# ESP32_with_USBC.net
KiCad netlist of a schematic drawn in Altium Designer
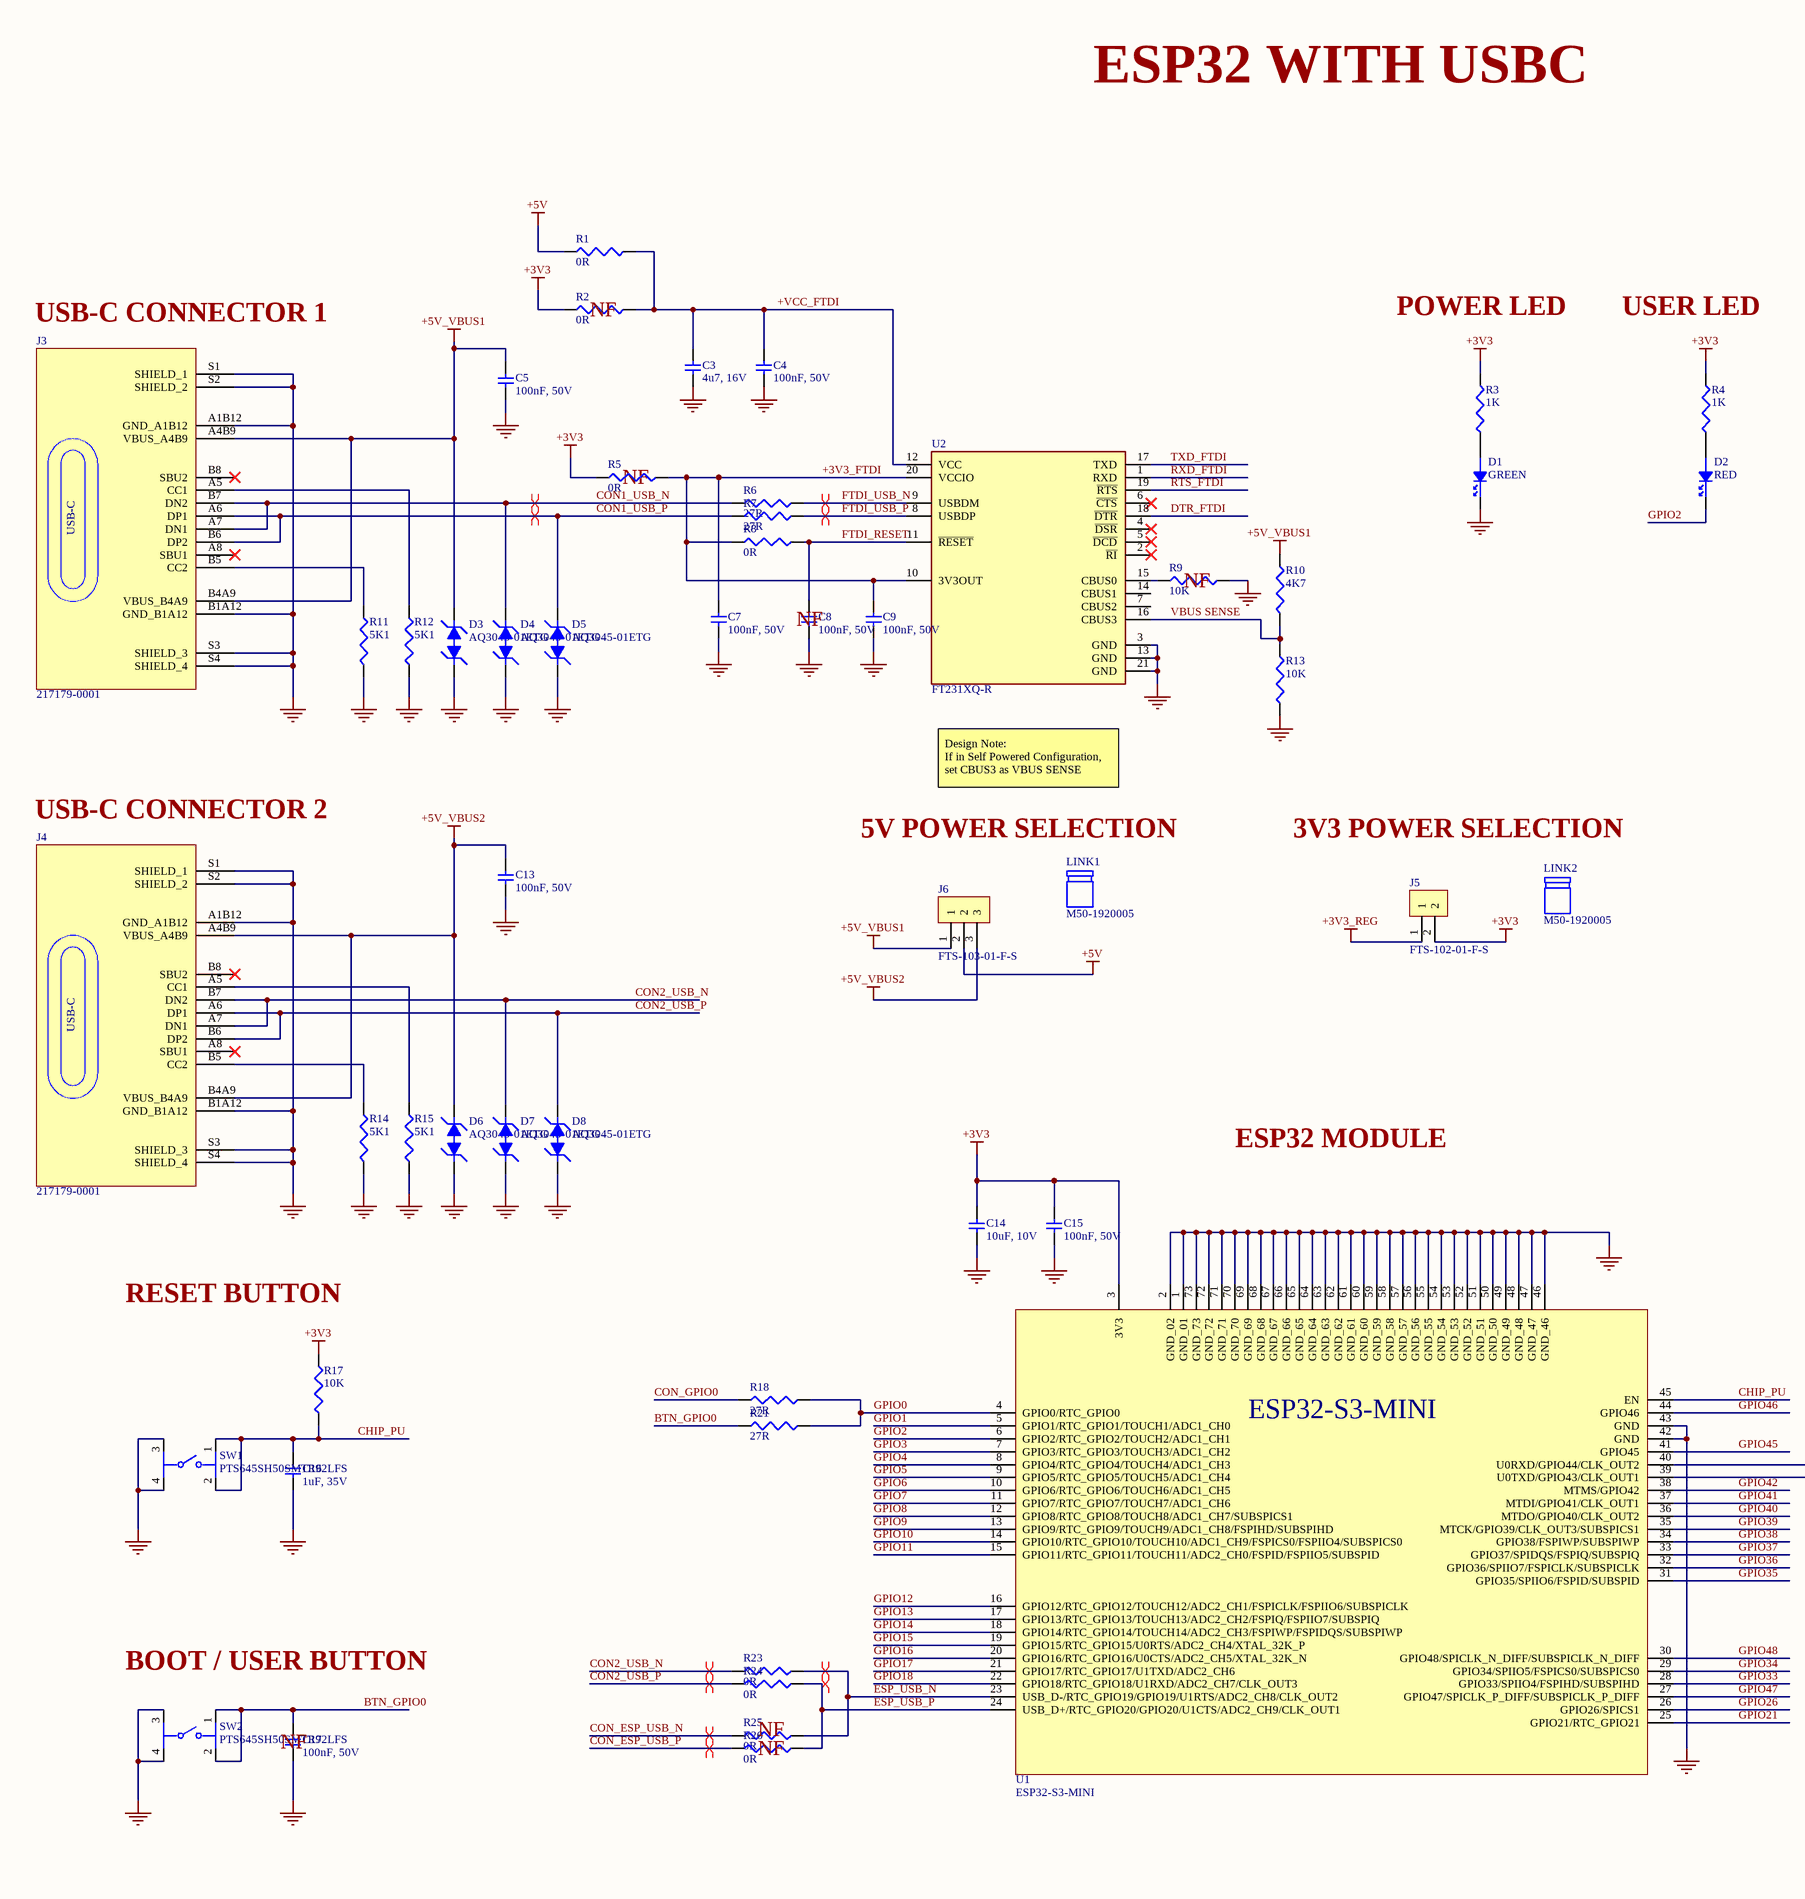
[diagram p0: ESP32 with USBC.SchDoc, left]
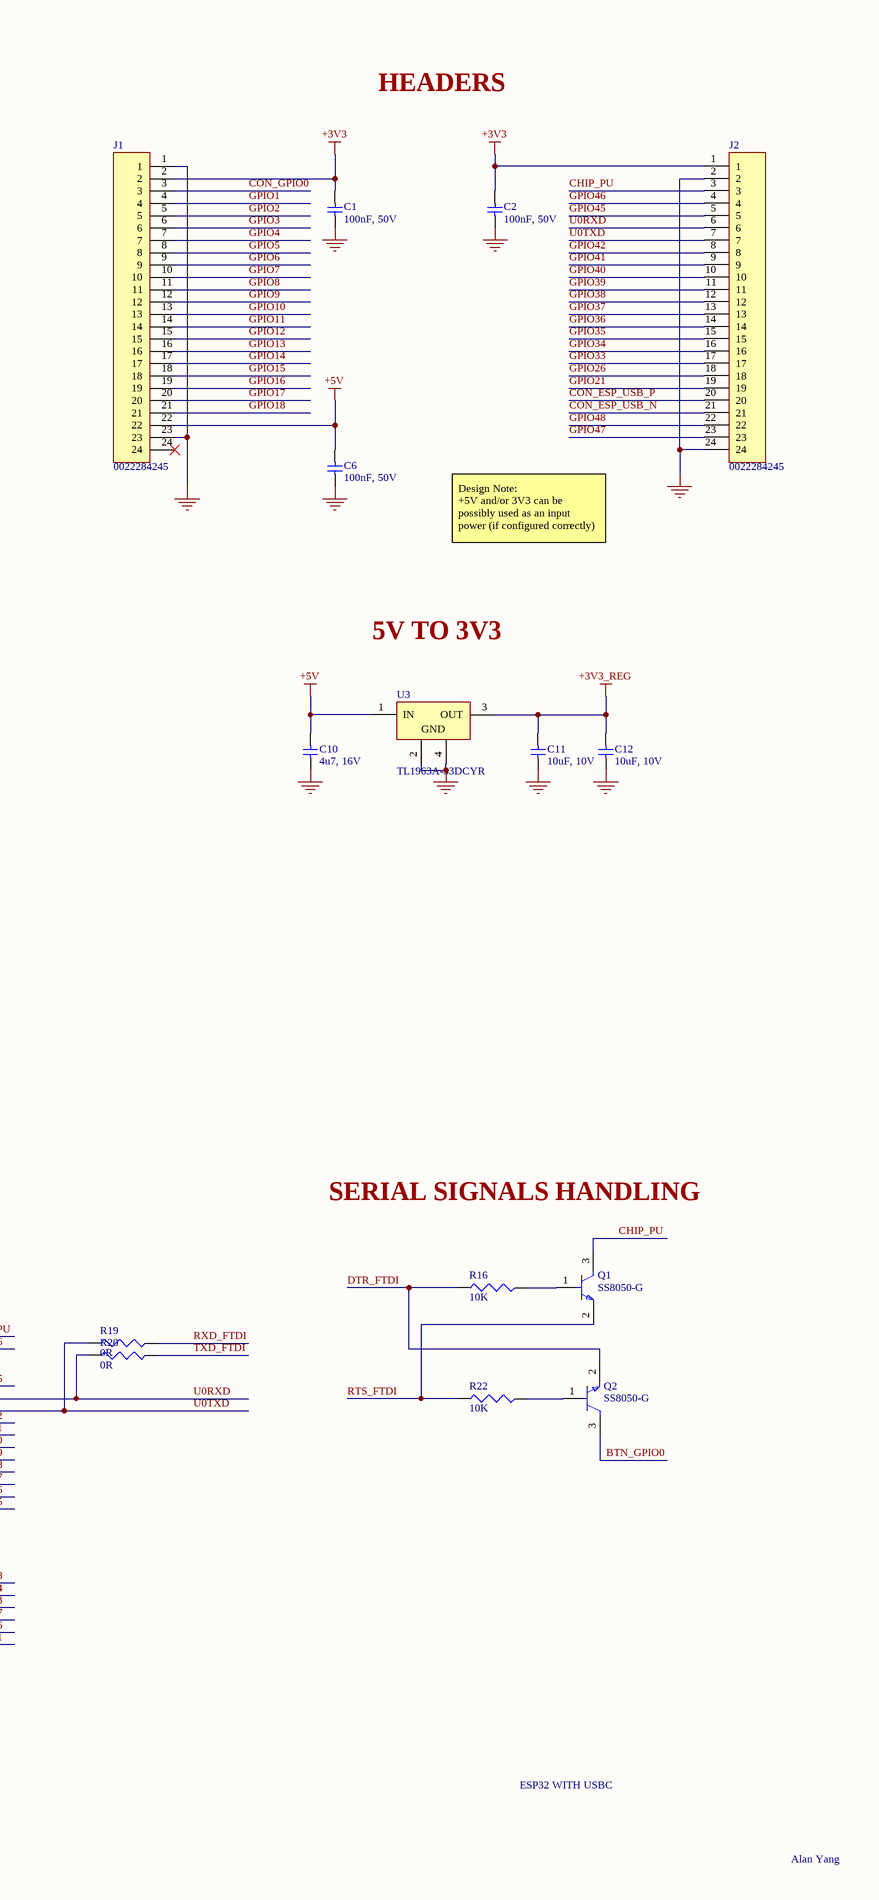
[diagram p1: ESP32 with USBC.SchDoc, right]

(export (version "E")
  (design (tool "Eeschema 10.0.6"))
  (components
    (comp (ref "C1")
      (value "100nF, 50V")
      (footprint "CAPC1005X55N")
      (description "CAP CER 0.1UF 50V X7R 0402")
      (fields
        (field (name "MANUFACTURER") "Samsung")
        (field (name "MANUFACTURER PART NUMBER") "CL05B104KB54PNC")
      )
      (libsource (lib "Schlib") (part "CL05B104KB54PNC"))
    )
    (comp (ref "C2")
      (value "100nF, 50V")
      (footprint "CAPC1005X55N")
      (description "CAP CER 0.1UF 50V X7R 0402")
      (fields
        (field (name "MANUFACTURER") "Samsung")
        (field (name "MANUFACTURER PART NUMBER") "CL05B104KB54PNC")
      )
      (libsource (lib "Schlib") (part "CL05B104KB54PNC"))
    )
    (comp (ref "C3")
      (value "4u7, 16V")
      (footprint "CAPC1005X55N")
      (description "CAP CER 4.7UF 16V X5R 0402")
      (fields
        (field (name "MANUFACTURER") "Samsung")
        (field (name "MANUFACTURER PART NUMBER") "CL05A475MO5NUNC")
      )
      (libsource (lib "Schlib") (part "CL05A475MO5NUNC"))
    )
    (comp (ref "C4")
      (value "100nF, 50V")
      (footprint "CAPC1005X55N")
      (description "CAP CER 0.1UF 50V X7R 0402")
      (fields
        (field (name "MANUFACTURER") "Samsung")
        (field (name "MANUFACTURER PART NUMBER") "CL05B104KB54PNC")
      )
      (libsource (lib "Schlib") (part "CL05B104KB54PNC"))
    )
    (comp (ref "C5")
      (value "100nF, 50V")
      (footprint "CAPC1005X55N")
      (description "CAP CER 0.1UF 50V X7R 0402")
      (fields
        (field (name "MANUFACTURER") "Samsung")
        (field (name "MANUFACTURER PART NUMBER") "CL05B104KB54PNC")
      )
      (libsource (lib "Schlib") (part "CL05B104KB54PNC"))
    )
    (comp (ref "C6")
      (value "100nF, 50V")
      (footprint "CAPC1005X55N")
      (description "CAP CER 0.1UF 50V X7R 0402")
      (fields
        (field (name "MANUFACTURER") "Samsung")
        (field (name "MANUFACTURER PART NUMBER") "CL05B104KB54PNC")
      )
      (libsource (lib "Schlib") (part "CL05B104KB54PNC"))
    )
    (comp (ref "C7")
      (value "100nF, 50V")
      (footprint "CAPC1005X55N")
      (description "CAP CER 0.1UF 50V X7R 0402")
      (fields
        (field (name "MANUFACTURER") "Samsung")
        (field (name "MANUFACTURER PART NUMBER") "CL05B104KB54PNC")
      )
      (libsource (lib "Schlib") (part "CL05B104KB54PNC"))
    )
    (comp (ref "C8")
      (value "100nF, 50V")
      (footprint "CAPC1005X55N")
      (description "CAP CER 0.1UF 50V X7R 0402")
      (fields
        (field (name "MANUFACTURER") "Samsung")
        (field (name "MANUFACTURER PART NUMBER") "CL05B104KB54PNC")
      )
      (libsource (lib "Schlib") (part "CL05B104KB54PNC"))
    )
    (comp (ref "C9")
      (value "100nF, 50V")
      (footprint "CAPC1005X55N")
      (description "CAP CER 0.1UF 50V X7R 0402")
      (fields
        (field (name "MANUFACTURER") "Samsung")
        (field (name "MANUFACTURER PART NUMBER") "CL05B104KB54PNC")
      )
      (libsource (lib "Schlib") (part "CL05B104KB54PNC"))
    )
    (comp (ref "C10")
      (value "4u7, 16V")
      (footprint "CAPC1005X55N")
      (description "CAP CER 4.7UF 16V X5R 0402")
      (fields
        (field (name "MANUFACTURER") "Samsung")
        (field (name "MANUFACTURER PART NUMBER") "CL05A475MO5NUNC")
      )
      (libsource (lib "Schlib") (part "CL05A475MO5NUNC"))
    )
    (comp (ref "C11")
      (value "10uF, 10V")
      (footprint "CAPC1005X55N")
      (description "CAP CER 10UF 10V X5R 0402")
      (fields
        (field (name "MANUFACTURER") "Samsung")
        (field (name "MANUFACTURER PART NUMBER") "CL05A106MP8NUB8")
      )
      (libsource (lib "Schlib") (part "CL05A106MP8NUB8"))
    )
    (comp (ref "C12")
      (value "10uF, 10V")
      (footprint "CAPC1005X55N")
      (description "CAP CER 10UF 10V X5R 0402")
      (fields
        (field (name "MANUFACTURER") "Samsung")
        (field (name "MANUFACTURER PART NUMBER") "CL05A106MP8NUB8")
      )
      (libsource (lib "Schlib") (part "CL05A106MP8NUB8"))
    )
    (comp (ref "C13")
      (value "100nF, 50V")
      (footprint "CAPC1005X55N")
      (description "CAP CER 0.1UF 50V X7R 0402")
      (fields
        (field (name "MANUFACTURER") "Samsung")
        (field (name "MANUFACTURER PART NUMBER") "CL05B104KB54PNC")
      )
      (libsource (lib "Schlib") (part "CL05B104KB54PNC"))
    )
    (comp (ref "C14")
      (value "10uF, 10V")
      (footprint "CAPC1005X55N")
      (description "CAP CER 10UF 10V X5R 0402")
      (fields
        (field (name "MANUFACTURER") "Samsung")
        (field (name "MANUFACTURER PART NUMBER") "CL05A106MP8NUB8")
      )
      (libsource (lib "Schlib") (part "CL05A106MP8NUB8"))
    )
    (comp (ref "C15")
      (value "100nF, 50V")
      (footprint "CAPC1005X55N")
      (description "CAP CER 0.1UF 50V X7R 0402")
      (fields
        (field (name "MANUFACTURER") "Samsung")
        (field (name "MANUFACTURER PART NUMBER") "CL05B104KB54PNC")
      )
      (libsource (lib "Schlib") (part "CL05B104KB54PNC"))
    )
    (comp (ref "C16")
      (value "1uF, 35V")
      (footprint "CAPC1005X55N")
      (description "CAP CER 1UF 35V X5R 0402")
      (fields
        (field (name "MANUFACTURER") "Samsung")
        (field (name "MANUFACTURER PART NUMBER") "CL05A105KL5NRNC")
      )
      (libsource (lib "Schlib") (part "CL05A105KL5NRNC"))
    )
    (comp (ref "C17")
      (value "100nF, 50V")
      (footprint "CAPC1005X55N")
      (description "CAP CER 0.1UF 50V X7R 0402")
      (fields
        (field (name "MANUFACTURER") "Samsung")
        (field (name "MANUFACTURER PART NUMBER") "CL05B104KB54PNC")
      )
      (libsource (lib "Schlib") (part "CL05B104KB54PNC"))
    )
    (comp (ref "D1")
      (value "GREEN")
      (footprint "LED0402G")
      (description "LED YLW-GRN 0402 SMD")
      (fields
        (field (name "MANUFACTURER") "Vishay")
        (field (name "MANUFACTURER PART NUMBER") "VLMG1500-GS08")
      )
      (libsource (lib "Schlib") (part "VLMG1500-GS08"))
    )
    (comp (ref "D2")
      (value "RED")
      (footprint "LED0402R")
      (description "LED RED 0402 SMD")
      (fields
        (field (name "MANUFACTURER") "Vishay")
        (field (name "MANUFACTURER PART NUMBER") "VLMS1500-GS08")
      )
      (libsource (lib "Schlib") (part "VLMS1500-GS08"))
    )
    (comp (ref "D3")
      (value "AQ3045-01ETG")
      (footprint "SOD882")
      (description "TVS DIODE 5.3VWM 12VC SOD882")
      (fields (field (name "MANUFACTURER") "Littelfuse") (field (name "LCSC PART NUMBER") "C3710326"))
      (libsource (lib "Schlib") (part "AQ3045-01ETG"))
    )
    (comp (ref "D4")
      (value "AQ3045-01ETG")
      (footprint "SOD882")
      (description "TVS DIODE 5.3VWM 12VC SOD882")
      (fields (field (name "MANUFACTURER") "Littelfuse") (field (name "LCSC PART NUMBER") "C3710326"))
      (libsource (lib "Schlib") (part "AQ3045-01ETG"))
    )
    (comp (ref "D5")
      (value "AQ3045-01ETG")
      (footprint "SOD882")
      (description "TVS DIODE 5.3VWM 12VC SOD882")
      (fields (field (name "MANUFACTURER") "Littelfuse") (field (name "LCSC PART NUMBER") "C3710326"))
      (libsource (lib "Schlib") (part "AQ3045-01ETG"))
    )
    (comp (ref "D6")
      (value "AQ3045-01ETG")
      (footprint "SOD882")
      (description "TVS DIODE 5.3VWM 12VC SOD882")
      (fields (field (name "MANUFACTURER") "Littelfuse") (field (name "LCSC PART NUMBER") "C3710326"))
      (libsource (lib "Schlib") (part "AQ3045-01ETG"))
    )
    (comp (ref "D7")
      (value "AQ3045-01ETG")
      (footprint "SOD882")
      (description "TVS DIODE 5.3VWM 12VC SOD882")
      (fields (field (name "MANUFACTURER") "Littelfuse") (field (name "LCSC PART NUMBER") "C3710326"))
      (libsource (lib "Schlib") (part "AQ3045-01ETG"))
    )
    (comp (ref "D8")
      (value "AQ3045-01ETG")
      (footprint "SOD882")
      (description "TVS DIODE 5.3VWM 12VC SOD882")
      (fields (field (name "MANUFACTURER") "Littelfuse") (field (name "LCSC PART NUMBER") "C3710326"))
      (libsource (lib "Schlib") (part "AQ3045-01ETG"))
    )
    (comp (ref "J1")
      (value "0022284245")
      (footprint "HDR_1X24_2.54MM")
      (description "CONN HEADER VERT 24POS 2.54MM")
      (fields (field (name "MANUFACTURER") "Molex") (field (name "MANUFACTURER PART NUMBER") "22-28-4245"))
      (libsource (lib "Schlib") (part "0022284245"))
    )
    (comp (ref "J2")
      (value "0022284245")
      (footprint "HDR_1X24_2.54MM")
      (description "CONN HEADER VERT 24POS 2.54MM")
      (fields (field (name "MANUFACTURER") "Molex") (field (name "MANUFACTURER PART NUMBER") "22-28-4245"))
      (libsource (lib "") (part "0022284245_1"))
    )
    (comp (ref "J3")
      (value "217179-0001")
      (footprint "FP-2171790001-MFG")
      (description "CONN RCP USB2.0 TYP C 24P SMD RA")
      (fields (field (name "MANUFACTURER") "Molex") (field (name "LCSC PART NUMBER") "C3197684"))
      (libsource (lib "Schlib") (part "217179-0001"))
    )
    (comp (ref "J4")
      (value "217179-0001")
      (footprint "FP-2171790001-MFG")
      (description "CONN RCP USB2.0 TYP C 24P SMD RA")
      (fields (field (name "MANUFACTURER") "Molex") (field (name "LCSC PART NUMBER") "C3197684"))
      (libsource (lib "Schlib") (part "217179-0001"))
    )
    (comp (ref "J5")
      (value "FTS-102-01-F-S")
      (footprint "HDR_1X2_1.27MM")
      (description "CONN HEADER VERT 2POS 1.27MM")
      (fields (field (name "MANUFACTURER") "Samtec") (field (name "LCSC PART NUMBER") "C6045317"))
      (libsource (lib "Schlib") (part "FTS-102-01-F-S"))
    )
    (comp (ref "J6")
      (value "FTS-103-01-F-S")
      (footprint "HDR_1X3_1.27MM")
      (description "CONN HEADER VERT 3POS 1.27MM")
      (fields (field (name "MANUFACTURER") "Samtec") (field (name "LCSC PART NUMBER") "C3333578"))
      (libsource (lib "Schlib") (part "FTS-103-01-F-S"))
    )
    (comp (ref "LINK1")
      (value "M50-1920005")
      (description "CONN SHUNT 1.27MM RED")
      (fields (field (name "MANUFACTURER") "Harwin") (field (name "LCSC PART NUMBER") "C6985646"))
      (libsource (lib "Schlib") (part "M50-1920005"))
    )
    (comp (ref "LINK2")
      (value "M50-1920005")
      (description "CONN SHUNT 1.27MM RED")
      (fields (field (name "MANUFACTURER") "Harwin") (field (name "LCSC PART NUMBER") "C6985646"))
      (libsource (lib "Schlib") (part "M50-1920005"))
    )
    (comp (ref "Q1")
      (value "SS8050-G")
      (footprint "FP-SS8050-G-IPC_B")
      (description "TRANS NPN 25V 1.5A SOT-23-3")
      (fields (field (name "MANUFACTURER") "Comchip") (field (name "LCSC PART NUMBER") "C164886"))
      (libsource (lib "Schlib") (part "SS8050-G"))
    )
    (comp (ref "Q2")
      (value "SS8050-G")
      (footprint "FP-SS8050-G-IPC_B")
      (description "TRANS NPN 25V 1.5A SOT-23-3")
      (fields (field (name "MANUFACTURER") "Comchip") (field (name "LCSC PART NUMBER") "C164886"))
      (libsource (lib "Schlib") (part "SS8050-G"))
    )
    (comp (ref "R1")
      (value "0R")
      (footprint "RESC1005X37N")
      (description "RES 0 OHM JUMPER 1/16W 0402")
      (fields
        (field (name "MANUFACTURER") "Yageo")
        (field (name "MANUFACTURER PART NUMBER") "RC0402JR-070RL")
      )
      (libsource (lib "Schlib") (part "RC0402JR-070RL"))
    )
    (comp (ref "R2")
      (value "0R")
      (footprint "RESC1005X37N")
      (description "RES 0 OHM JUMPER 1/16W 0402")
      (fields
        (field (name "MANUFACTURER") "Yageo")
        (field (name "MANUFACTURER PART NUMBER") "RC0402JR-070RL")
      )
      (libsource (lib "Schlib") (part "RC0402JR-070RL"))
    )
    (comp (ref "R3")
      (value "1K")
      (footprint "RESC1005X37N")
      (description "RES 1K OHM 1% 1/16W 0402")
      (fields
        (field (name "MANUFACTURER") "Yageo")
        (field (name "MANUFACTURER PART NUMBER") "RC0402FR-071KL")
      )
      (libsource (lib "Schlib") (part "RC0402FR-071KL"))
    )
    (comp (ref "R4")
      (value "1K")
      (footprint "RESC1005X37N")
      (description "RES 1K OHM 1% 1/16W 0402")
      (fields
        (field (name "MANUFACTURER") "Yageo")
        (field (name "MANUFACTURER PART NUMBER") "RC0402FR-071KL")
      )
      (libsource (lib "Schlib") (part "RC0402FR-071KL"))
    )
    (comp (ref "R5")
      (value "0R")
      (footprint "RESC1005X37N")
      (description "RES 0 OHM JUMPER 1/16W 0402")
      (fields
        (field (name "MANUFACTURER") "Yageo")
        (field (name "MANUFACTURER PART NUMBER") "RC0402JR-070RL")
      )
      (libsource (lib "Schlib") (part "RC0402JR-070RL"))
    )
    (comp (ref "R6")
      (value "27R")
      (footprint "RESC1005X37N")
      (description "RES 27.4 OHM 1% 1/16W 0402")
      (fields
        (field (name "MANUFACTURER") "Yageo")
        (field (name "MANUFACTURER PART NUMBER") "RC0402FR-0727R4L")
      )
      (libsource (lib "Schlib") (part "RC0402FR-0727R4L"))
    )
    (comp (ref "R7")
      (value "27R")
      (footprint "RESC1005X37N")
      (description "RES 27.4 OHM 1% 1/16W 0402")
      (fields
        (field (name "MANUFACTURER") "Yageo")
        (field (name "MANUFACTURER PART NUMBER") "RC0402FR-0727R4L")
      )
      (libsource (lib "Schlib") (part "RC0402FR-0727R4L"))
    )
    (comp (ref "R8")
      (value "0R")
      (footprint "RESC1005X37N")
      (description "RES 0 OHM JUMPER 1/16W 0402")
      (fields
        (field (name "MANUFACTURER") "Yageo")
        (field (name "MANUFACTURER PART NUMBER") "RC0402JR-070RL")
      )
      (libsource (lib "Schlib") (part "RC0402JR-070RL"))
    )
    (comp (ref "R9")
      (value "10K")
      (footprint "RESC1005X37N")
      (description "RES SMD 10K OHM 1% 1/16W 0402")
      (fields
        (field (name "MANUFACTURER") "Yageo")
        (field (name "MANUFACTURER PART NUMBER") "AC0402FR-0710KL")
      )
      (libsource (lib "Schlib") (part "AC0402FR-0710KL"))
    )
    (comp (ref "R10")
      (value "4K7")
      (footprint "RESC1005X37N")
      (description "RES 4.7K OHM 1% 1/16W 0402")
      (fields
        (field (name "MANUFACTURER") "Yageo")
        (field (name "MANUFACTURER PART NUMBER") "RC0402FR-074K7L")
      )
      (libsource (lib "Schlib") (part "RC0402FR-074K7L"))
    )
    (comp (ref "R11")
      (value "5K1")
      (footprint "RESC1005X37N")
      (description "RES SMD 5.1K OHM 1% 1/16W 0402")
      (fields
        (field (name "MANUFACTURER") "Yageo")
        (field (name "MANUFACTURER PART NUMBER") "AC0402FR-075K1L")
      )
      (libsource (lib "Schlib") (part "AC0402FR-075K1L"))
    )
    (comp (ref "R12")
      (value "5K1")
      (footprint "RESC1005X37N")
      (description "RES SMD 5.1K OHM 1% 1/16W 0402")
      (fields
        (field (name "MANUFACTURER") "Yageo")
        (field (name "MANUFACTURER PART NUMBER") "AC0402FR-075K1L")
      )
      (libsource (lib "Schlib") (part "AC0402FR-075K1L"))
    )
    (comp (ref "R13")
      (value "10K")
      (footprint "RESC1005X37N")
      (description "RES SMD 10K OHM 1% 1/16W 0402")
      (fields
        (field (name "MANUFACTURER") "Yageo")
        (field (name "MANUFACTURER PART NUMBER") "AC0402FR-0710KL")
      )
      (libsource (lib "Schlib") (part "AC0402FR-0710KL"))
    )
    (comp (ref "R14")
      (value "5K1")
      (footprint "RESC1005X37N")
      (description "RES SMD 5.1K OHM 1% 1/16W 0402")
      (fields
        (field (name "MANUFACTURER") "Yageo")
        (field (name "MANUFACTURER PART NUMBER") "AC0402FR-075K1L")
      )
      (libsource (lib "Schlib") (part "AC0402FR-075K1L"))
    )
    (comp (ref "R15")
      (value "5K1")
      (footprint "RESC1005X37N")
      (description "RES SMD 5.1K OHM 1% 1/16W 0402")
      (fields
        (field (name "MANUFACTURER") "Yageo")
        (field (name "MANUFACTURER PART NUMBER") "AC0402FR-075K1L")
      )
      (libsource (lib "Schlib") (part "AC0402FR-075K1L"))
    )
    (comp (ref "R16")
      (value "10K")
      (footprint "RESC1005X37N")
      (description "RES SMD 10K OHM 1% 1/16W 0402")
      (fields
        (field (name "MANUFACTURER") "Yageo")
        (field (name "MANUFACTURER PART NUMBER") "AC0402FR-0710KL")
      )
      (libsource (lib "Schlib") (part "AC0402FR-0710KL"))
    )
    (comp (ref "R17")
      (value "10K")
      (footprint "RESC1005X37N")
      (description "RES SMD 10K OHM 1% 1/16W 0402")
      (fields
        (field (name "MANUFACTURER") "Yageo")
        (field (name "MANUFACTURER PART NUMBER") "AC0402FR-0710KL")
      )
      (libsource (lib "Schlib") (part "AC0402FR-0710KL"))
    )
    (comp (ref "R18")
      (value "27R")
      (footprint "RESC1005X37N")
      (description "RES 27.4 OHM 1% 1/16W 0402")
      (fields
        (field (name "MANUFACTURER") "Yageo")
        (field (name "MANUFACTURER PART NUMBER") "RC0402FR-0727R4L")
      )
      (libsource (lib "Schlib") (part "RC0402FR-0727R4L"))
    )
    (comp (ref "R19")
      (value "0R")
      (footprint "RESC1005X37N")
      (description "RES 0 OHM JUMPER 1/16W 0402")
      (fields
        (field (name "MANUFACTURER") "Yageo")
        (field (name "MANUFACTURER PART NUMBER") "RC0402JR-070RL")
      )
      (libsource (lib "Schlib") (part "RC0402JR-070RL"))
    )
    (comp (ref "R20")
      (value "0R")
      (footprint "RESC1005X37N")
      (description "RES 0 OHM JUMPER 1/16W 0402")
      (fields
        (field (name "MANUFACTURER") "Yageo")
        (field (name "MANUFACTURER PART NUMBER") "RC0402JR-070RL")
      )
      (libsource (lib "Schlib") (part "RC0402JR-070RL"))
    )
    (comp (ref "R21")
      (value "27R")
      (footprint "RESC1005X37N")
      (description "RES 27.4 OHM 1% 1/16W 0402")
      (fields
        (field (name "MANUFACTURER") "Yageo")
        (field (name "MANUFACTURER PART NUMBER") "RC0402FR-0727R4L")
      )
      (libsource (lib "Schlib") (part "RC0402FR-0727R4L"))
    )
    (comp (ref "R22")
      (value "10K")
      (footprint "RESC1005X37N")
      (description "RES SMD 10K OHM 1% 1/16W 0402")
      (fields
        (field (name "MANUFACTURER") "Yageo")
        (field (name "MANUFACTURER PART NUMBER") "AC0402FR-0710KL")
      )
      (libsource (lib "Schlib") (part "AC0402FR-0710KL"))
    )
    (comp (ref "R23")
      (value "0R")
      (footprint "RESC1005X37N")
      (description "RES 0 OHM JUMPER 1/16W 0402")
      (fields
        (field (name "MANUFACTURER") "Yageo")
        (field (name "MANUFACTURER PART NUMBER") "RC0402JR-070RL")
      )
      (libsource (lib "Schlib") (part "RC0402JR-070RL"))
    )
    (comp (ref "R24")
      (value "0R")
      (footprint "RESC1005X37N")
      (description "RES 0 OHM JUMPER 1/16W 0402")
      (fields
        (field (name "MANUFACTURER") "Yageo")
        (field (name "MANUFACTURER PART NUMBER") "RC0402JR-070RL")
      )
      (libsource (lib "Schlib") (part "RC0402JR-070RL"))
    )
    (comp (ref "R25")
      (value "0R")
      (footprint "RESC1005X37N")
      (description "RES 0 OHM JUMPER 1/16W 0402")
      (fields
        (field (name "MANUFACTURER") "Yageo")
        (field (name "MANUFACTURER PART NUMBER") "RC0402JR-070RL")
      )
      (libsource (lib "Schlib") (part "RC0402JR-070RL"))
    )
    (comp (ref "R26")
      (value "0R")
      (footprint "RESC1005X37N")
      (description "RES 0 OHM JUMPER 1/16W 0402")
      (fields
        (field (name "MANUFACTURER") "Yageo")
        (field (name "MANUFACTURER PART NUMBER") "RC0402JR-070RL")
      )
      (libsource (lib "Schlib") (part "RC0402JR-070RL"))
    )
    (comp (ref "SW1")
      (value "PTS645SH50SMTR92LFS")
      (footprint "FP-PTS645SH50SMTR92LFS-MFG")
      (description "SWITCH TACTILE SPST-NO 0.05A 12V")
      (fields (field (name "MANUFACTURER") "ITT C&K") (field (name "LCSC PART NUMBER") "C221869"))
      (libsource (lib "Schlib") (part "PTS645SH50SMTR92LFS"))
    )
    (comp (ref "SW2")
      (value "PTS645SH50SMTR92LFS")
      (footprint "FP-PTS645SH50SMTR92LFS-MFG")
      (description "SWITCH TACTILE SPST-NO 0.05A 12V")
      (fields (field (name "MANUFACTURER") "ITT C&K") (field (name "LCSC PART NUMBER") "C221869"))
      (libsource (lib "Schlib") (part "PTS645SH50SMTR92LFS"))
    )
    (comp (ref "U1")
      (value "ESP32-S3-MINI")
      (footprint "XCVR_ESP32-S3-MINI-1-N8")
      (description "SMD module, ESP32-S3FN8, 8 MB SPI flash, PCB antenna")
      (fields
        (field (name "MANUFACTURER") "Espressif Systems")
        (field (name "MANUFACTURER PART NUMBER") "ESP32-S3-MINI-1-N8")
      )
      (libsource (lib "Schlib") (part "ESP32-S3-MINI-1-N8"))
    )
    (comp (ref "U2")
      (value "FT231XQ-R")
      (footprint "FP-QFN-20-IPC_B")
      (description "IC USB SERIAL FULL UART 20QFN")
      (fields (field (name "MANUFACTURER") "FTDI") (field (name "LCSC PART NUMBER") "C132159"))
      (libsource (lib "Schlib") (part "FT231XQ-R"))
    )
    (comp (ref "U3")
      (value "TL1963A-33DCYR")
      (footprint "DCY0004A_N")
      (description "IC REG LIN 3.3V 1.5A SOT-223-4")
      (fields (field (name "MANUFACTURER") "Texas Instruments") (field (name "LCSC PART NUMBER") "C181262"))
      (libsource (lib "Schlib") (part "TL1963A-33DCYR"))
    )
  )
  (nets
    (net (code "1") (name "+3V3") (class "Default")
      (node (ref "C1") (pin "2") (pinfunction "2_2") (pintype "passive"))
      (node (ref "C14") (pin "2") (pinfunction "2_2") (pintype "passive"))
      (node (ref "C15") (pin "2") (pinfunction "2_2") (pintype "passive"))
      (node (ref "C2") (pin "2") (pinfunction "2_2") (pintype "passive"))
      (node (ref "J1") (pin "2") (pinfunction "2_2") (pintype "passive"))
      (node (ref "J2") (pin "1") (pinfunction "1_1") (pintype "passive"))
      (node (ref "J5") (pin "2") (pinfunction "2_2") (pintype "passive"))
      (node (ref "R17") (pin "2") (pinfunction "2_2") (pintype "passive"))
      (node (ref "R2") (pin "1") (pinfunction "1_1") (pintype "passive"))
      (node (ref "R3") (pin "2") (pinfunction "2_2") (pintype "passive"))
      (node (ref "R4") (pin "2") (pinfunction "2_2") (pintype "passive"))
      (node (ref "R5") (pin "1") (pinfunction "1_1") (pintype "passive"))
      (node (ref "U1") (pin "3") (pinfunction "3V3_3") (pintype "passive"))
    )
    (net (code "2") (name "+3V3_REG") (class "Default")
      (node (ref "C11") (pin "2") (pinfunction "2_2") (pintype "passive"))
      (node (ref "C12") (pin "2") (pinfunction "2_2") (pintype "passive"))
      (node (ref "J5") (pin "1") (pinfunction "1_1") (pintype "passive"))
      (node (ref "U3") (pin "3") (pinfunction "OUT_3") (pintype "power_in"))
    )
    (net (code "3") (name "+5V") (class "Default")
      (node (ref "C10") (pin "2") (pinfunction "2_2") (pintype "passive"))
      (node (ref "C6") (pin "2") (pinfunction "2_2") (pintype "passive"))
      (node (ref "J1") (pin "22") (pinfunction "22_22") (pintype "passive"))
      (node (ref "J6") (pin "2") (pinfunction "2_2") (pintype "passive"))
      (node (ref "R1") (pin "1") (pinfunction "1_1") (pintype "passive"))
      (node (ref "U3") (pin "1") (pinfunction "IN_1") (pintype "power_in"))
    )
    (net (code "4") (name "+5V_VBUS1") (class "Default")
      (node (ref "C5") (pin "2") (pinfunction "2_2") (pintype "passive"))
      (node (ref "D3") (pin "2") (pinfunction "2_2") (pintype "passive"))
      (node (ref "J3") (pin "A4B9") (pinfunction "VBUS_A4B9_A4B9") (pintype "passive"))
      (node (ref "J3") (pin "B4A9") (pinfunction "VBUS_B4A9_B4A9") (pintype "passive"))
      (node (ref "J6") (pin "1") (pinfunction "1_1") (pintype "passive"))
      (node (ref "R10") (pin "2") (pinfunction "2_2") (pintype "passive"))
    )
    (net (code "5") (name "+5V_VBUS2") (class "Default")
      (node (ref "C13") (pin "2") (pinfunction "2_2") (pintype "passive"))
      (node (ref "D6") (pin "2") (pinfunction "2_2") (pintype "passive"))
      (node (ref "J4") (pin "A4B9") (pinfunction "VBUS_A4B9_A4B9") (pintype "passive"))
      (node (ref "J4") (pin "B4A9") (pinfunction "VBUS_B4A9_B4A9") (pintype "passive"))
      (node (ref "J6") (pin "3") (pinfunction "3_3") (pintype "passive"))
    )
    (net (code "6") (name "/+3V3_FTDI") (class "Default")
      (node (ref "C7") (pin "2") (pinfunction "2_2") (pintype "passive"))
      (node (ref "C9") (pin "2") (pinfunction "2_2") (pintype "passive"))
      (node (ref "R5") (pin "2") (pinfunction "2_2") (pintype "passive"))
      (node (ref "R8") (pin "1") (pinfunction "1_1") (pintype "passive"))
      (node (ref "U2") (pin "10") (pinfunction "3V3OUT_10") (pintype "passive"))
      (node (ref "U2") (pin "20") (pinfunction "VCCIO_20") (pintype "passive"))
    )
    (net (code "7") (name "/+VCC_FTDI") (class "Default")
      (node (ref "C3") (pin "1") (pinfunction "1_1") (pintype "passive"))
      (node (ref "C4") (pin "2") (pinfunction "2_2") (pintype "passive"))
      (node (ref "R1") (pin "2") (pinfunction "2_2") (pintype "passive"))
      (node (ref "R2") (pin "2") (pinfunction "2_2") (pintype "passive"))
      (node (ref "U2") (pin "12") (pinfunction "VCC_12") (pintype "passive"))
    )
    (net (code "8") (name "/BTN_GPIO0") (class "Default")
      (node (ref "C17") (pin "2") (pinfunction "2_2") (pintype "passive"))
      (node (ref "Q2") (pin "3") (pinfunction "C_3") (pintype "passive"))
      (node (ref "R21") (pin "1") (pinfunction "1_1") (pintype "passive"))
      (node (ref "SW2") (pin "1") (pinfunction "1_1") (pintype "passive"))
      (node (ref "SW2") (pin "2") (pinfunction "2_2") (pintype "passive"))
    )
    (net (code "9") (name "/CHIP_PU") (class "Default")
      (node (ref "C16") (pin "2") (pinfunction "2_2") (pintype "passive"))
      (node (ref "J2") (pin "3") (pinfunction "3_3") (pintype "passive"))
      (node (ref "Q1") (pin "3") (pinfunction "C_3") (pintype "passive"))
      (node (ref "R17") (pin "1") (pinfunction "1_1") (pintype "passive"))
      (node (ref "SW1") (pin "1") (pinfunction "1_1") (pintype "passive"))
      (node (ref "SW1") (pin "2") (pinfunction "2_2") (pintype "passive"))
      (node (ref "U1") (pin "45") (pinfunction "EN_45") (pintype "passive"))
    )
    (net (code "10") (name "/CON1_USB_N") (class "Default")
      (node (ref "D4") (pin "2") (pinfunction "2_2") (pintype "passive"))
      (node (ref "J3") (pin "A7") (pinfunction "DN1_A7") (pintype "passive"))
      (node (ref "J3") (pin "B7") (pinfunction "DN2_B7") (pintype "passive"))
      (node (ref "R6") (pin "1") (pinfunction "1_1") (pintype "passive"))
    )
    (net (code "11") (name "/CON1_USB_P") (class "Default")
      (node (ref "D5") (pin "2") (pinfunction "2_2") (pintype "passive"))
      (node (ref "J3") (pin "A6") (pinfunction "DP1_A6") (pintype "passive"))
      (node (ref "J3") (pin "B6") (pinfunction "DP2_B6") (pintype "passive"))
      (node (ref "R7") (pin "1") (pinfunction "1_1") (pintype "passive"))
    )
    (net (code "12") (name "/CON2_USB_N") (class "Default")
      (node (ref "D7") (pin "2") (pinfunction "2_2") (pintype "passive"))
      (node (ref "J4") (pin "A7") (pinfunction "DN1_A7") (pintype "passive"))
      (node (ref "J4") (pin "B7") (pinfunction "DN2_B7") (pintype "passive"))
      (node (ref "R23") (pin "1") (pinfunction "1_1") (pintype "passive"))
    )
    (net (code "13") (name "/CON2_USB_P") (class "Default")
      (node (ref "D8") (pin "2") (pinfunction "2_2") (pintype "passive"))
      (node (ref "J4") (pin "A6") (pinfunction "DP1_A6") (pintype "passive"))
      (node (ref "J4") (pin "B6") (pinfunction "DP2_B6") (pintype "passive"))
      (node (ref "R24") (pin "1") (pinfunction "1_1") (pintype "passive"))
    )
    (net (code "14") (name "/CON_ESP_USB_N") (class "Default")
      (node (ref "J2") (pin "21") (pinfunction "21_21") (pintype "passive"))
      (node (ref "R25") (pin "1") (pinfunction "1_1") (pintype "passive"))
    )
    (net (code "15") (name "/CON_ESP_USB_P") (class "Default")
      (node (ref "J2") (pin "20") (pinfunction "20_20") (pintype "passive"))
      (node (ref "R26") (pin "1") (pinfunction "1_1") (pintype "passive"))
    )
    (net (code "16") (name "/CON_GPIO0") (class "Default")
      (node (ref "J1") (pin "3") (pinfunction "3_3") (pintype "passive"))
      (node (ref "R18") (pin "1") (pinfunction "1_1") (pintype "passive"))
    )
    (net (code "17") (name "/DTR_FTDI") (class "Default")
      (node (ref "Q2") (pin "2") (pinfunction "E_2") (pintype "passive"))
      (node (ref "R16") (pin "1") (pinfunction "1_1") (pintype "passive"))
      (node (ref "U2") (pin "18") (pinfunction "~{DTR}_18") (pintype "passive"))
    )
    (net (code "18") (name "/ESP_USB_N") (class "Default")
      (node (ref "R23") (pin "2") (pinfunction "2_2") (pintype "passive"))
      (node (ref "R25") (pin "2") (pinfunction "2_2") (pintype "passive"))
      (node (ref "U1") (pin "23") (pinfunction "USB_D-/RTC_GPIO19/GPIO19/U1RTS/ADC2_CH8/CLK_OUT2_23") (pintype "passive"))
    )
    (net (code "19") (name "/ESP_USB_P") (class "Default")
      (node (ref "R24") (pin "2") (pinfunction "2_2") (pintype "passive"))
      (node (ref "R26") (pin "2") (pinfunction "2_2") (pintype "passive"))
      (node (ref "U1") (pin "24") (pinfunction "USB_D+/RTC_GPIO20/GPIO20/U1CTS/ADC2_CH9/CLK_OUT1_24") (pintype "passive"))
    )
    (net (code "20") (name "/FTDI_RESET") (class "Default")
      (node (ref "C8") (pin "2") (pinfunction "2_2") (pintype "passive"))
      (node (ref "R8") (pin "2") (pinfunction "2_2") (pintype "passive"))
      (node (ref "U2") (pin "11") (pinfunction "~{RESET}_11") (pintype "passive"))
    )
    (net (code "21") (name "/FTDI_USB_N") (class "Default")
      (node (ref "R6") (pin "2") (pinfunction "2_2") (pintype "passive"))
      (node (ref "U2") (pin "9") (pinfunction "USBDM_9") (pintype "passive"))
    )
    (net (code "22") (name "/FTDI_USB_P") (class "Default")
      (node (ref "R7") (pin "2") (pinfunction "2_2") (pintype "passive"))
      (node (ref "U2") (pin "8") (pinfunction "USBDP_8") (pintype "passive"))
    )
    (net (code "23") (name "/GPIO0") (class "Default")
      (node (ref "R18") (pin "2") (pinfunction "2_2") (pintype "passive"))
      (node (ref "R21") (pin "2") (pinfunction "2_2") (pintype "passive"))
      (node (ref "U1") (pin "4") (pinfunction "GPIO0/RTC_GPIO0_4") (pintype "passive"))
    )
    (net (code "24") (name "/GPIO1") (class "Default")
      (node (ref "J1") (pin "4") (pinfunction "4_4") (pintype "passive"))
      (node (ref "U1") (pin "5") (pinfunction "GPIO1/RTC_GPIO1/TOUCH1/ADC1_CH0_5") (pintype "passive"))
    )
    (net (code "25") (name "/GPIO2") (class "Default")
      (node (ref "D2") (pin "1") (pinfunction "1_1") (pintype "passive"))
      (node (ref "J1") (pin "5") (pinfunction "5_5") (pintype "passive"))
      (node (ref "U1") (pin "6") (pinfunction "GPIO2/RTC_GPIO2/TOUCH2/ADC1_CH1_6") (pintype "passive"))
    )
    (net (code "26") (name "/GPIO3") (class "Default")
      (node (ref "J1") (pin "6") (pinfunction "6_6") (pintype "passive"))
      (node (ref "U1") (pin "7") (pinfunction "GPIO3/RTC_GPIO3/TOUCH3/ADC1_CH2_7") (pintype "passive"))
    )
    (net (code "27") (name "/GPIO4") (class "Default")
      (node (ref "J1") (pin "7") (pinfunction "7_7") (pintype "passive"))
      (node (ref "U1") (pin "8") (pinfunction "GPIO4/RTC_GPIO4/TOUCH4/ADC1_CH3_8") (pintype "passive"))
    )
    (net (code "28") (name "/GPIO5") (class "Default")
      (node (ref "J1") (pin "8") (pinfunction "8_8") (pintype "passive"))
      (node (ref "U1") (pin "9") (pinfunction "GPIO5/RTC_GPIO5/TOUCH5/ADC1_CH4_9") (pintype "passive"))
    )
    (net (code "29") (name "/GPIO6") (class "Default")
      (node (ref "J1") (pin "9") (pinfunction "9_9") (pintype "passive"))
      (node (ref "U1") (pin "10") (pinfunction "GPIO6/RTC_GPIO6/TOUCH6/ADC1_CH5_10") (pintype "passive"))
    )
    (net (code "30") (name "/GPIO7") (class "Default")
      (node (ref "J1") (pin "10") (pinfunction "10_10") (pintype "passive"))
      (node (ref "U1") (pin "11") (pinfunction "GPIO7/RTC_GPIO7/TOUCH7/ADC1_CH6_11") (pintype "passive"))
    )
    (net (code "31") (name "/GPIO8") (class "Default")
      (node (ref "J1") (pin "11") (pinfunction "11_11") (pintype "passive"))
      (node (ref "U1") (pin "12") (pinfunction "GPIO8/RTC_GPIO8/TOUCH8/ADC1_CH7/SUBSPICS1_12") (pintype "passive"))
    )
    (net (code "32") (name "/GPIO9") (class "Default")
      (node (ref "J1") (pin "12") (pinfunction "12_12") (pintype "passive"))
      (node (ref "U1") (pin "13") (pinfunction "GPIO9/RTC_GPIO9/TOUCH9/ADC1_CH8/FSPIHD/SUBSPIHD_13") (pintype "passive"))
    )
    (net (code "33") (name "/GPIO10") (class "Default")
      (node (ref "J1") (pin "13") (pinfunction "13_13") (pintype "passive"))
      (node (ref "U1") (pin "14") (pinfunction "GPIO10/RTC_GPIO10/TOUCH10/ADC1_CH9/FSPICS0/FSPIIO4/SUBSPICS0_14") (pintype "passive"))
    )
    (net (code "34") (name "/GPIO11") (class "Default")
      (node (ref "J1") (pin "14") (pinfunction "14_14") (pintype "passive"))
      (node (ref "U1") (pin "15") (pinfunction "GPIO11/RTC_GPIO11/TOUCH11/ADC2_CH0/FSPID/FSPIIO5/SUBSPID_15") (pintype "passive"))
    )
    (net (code "35") (name "/GPIO12") (class "Default")
      (node (ref "J1") (pin "15") (pinfunction "15_15") (pintype "passive"))
      (node (ref "U1") (pin "16") (pinfunction "GPIO12/RTC_GPIO12/TOUCH12/ADC2_CH1/FSPICLK/FSPIIO6/SUBSPICLK_16") (pintype "passive"))
    )
    (net (code "36") (name "/GPIO13") (class "Default")
      (node (ref "J1") (pin "16") (pinfunction "16_16") (pintype "passive"))
      (node (ref "U1") (pin "17") (pinfunction "GPIO13/RTC_GPIO13/TOUCH13/ADC2_CH2/FSPIQ/FSPIIO7/SUBSPIQ_17") (pintype "passive"))
    )
    (net (code "37") (name "/GPIO14") (class "Default")
      (node (ref "J1") (pin "17") (pinfunction "17_17") (pintype "passive"))
      (node (ref "U1") (pin "18") (pinfunction "GPIO14/RTC_GPIO14/TOUCH14/ADC2_CH3/FSPIWP/FSPIDQS/SUBSPIWP_18") (pintype "passive"))
    )
    (net (code "38") (name "/GPIO15") (class "Default")
      (node (ref "J1") (pin "18") (pinfunction "18_18") (pintype "passive"))
      (node (ref "U1") (pin "19") (pinfunction "GPIO15/RTC_GPIO15/U0RTS/ADC2_CH4/XTAL_32K_P_19") (pintype "passive"))
    )
    (net (code "39") (name "/GPIO16") (class "Default")
      (node (ref "J1") (pin "19") (pinfunction "19_19") (pintype "passive"))
      (node (ref "U1") (pin "20") (pinfunction "GPIO16/RTC_GPIO16/U0CTS/ADC2_CH5/XTAL_32K_N_20") (pintype "passive"))
    )
    (net (code "40") (name "/GPIO17") (class "Default")
      (node (ref "J1") (pin "20") (pinfunction "20_20") (pintype "passive"))
      (node (ref "U1") (pin "21") (pinfunction "GPIO17/RTC_GPIO17/U1TXD/ADC2_CH6_21") (pintype "passive"))
    )
    (net (code "41") (name "/GPIO18") (class "Default")
      (node (ref "J1") (pin "21") (pinfunction "21_21") (pintype "passive"))
      (node (ref "U1") (pin "22") (pinfunction "GPIO18/RTC_GPIO18/U1RXD/ADC2_CH7/CLK_OUT3_22") (pintype "passive"))
    )
    (net (code "42") (name "/GPIO21") (class "Default")
      (node (ref "J2") (pin "19") (pinfunction "19_19") (pintype "passive"))
      (node (ref "U1") (pin "25") (pinfunction "GPIO21/RTC_GPIO21_25") (pintype "passive"))
    )
    (net (code "43") (name "/GPIO26") (class "Default")
      (node (ref "J2") (pin "18") (pinfunction "18_18") (pintype "passive"))
      (node (ref "U1") (pin "26") (pinfunction "GPIO26/SPICS1_26") (pintype "passive"))
    )
    (net (code "44") (name "/GPIO33") (class "Default")
      (node (ref "J2") (pin "17") (pinfunction "17_17") (pintype "passive"))
      (node (ref "U1") (pin "28") (pinfunction "GPIO33/SPIIO4/FSPIHD/SUBSPIHD_28") (pintype "passive"))
    )
    (net (code "45") (name "/GPIO34") (class "Default")
      (node (ref "J2") (pin "16") (pinfunction "16_16") (pintype "passive"))
      (node (ref "U1") (pin "29") (pinfunction "GPIO34/SPIIO5/FSPICS0/SUBSPICS0_29") (pintype "passive"))
    )
    (net (code "46") (name "/GPIO35") (class "Default")
      (node (ref "J2") (pin "15") (pinfunction "15_15") (pintype "passive"))
      (node (ref "U1") (pin "31") (pinfunction "GPIO35/SPIIO6/FSPID/SUBSPID_31") (pintype "passive"))
    )
    (net (code "47") (name "/GPIO36") (class "Default")
      (node (ref "J2") (pin "14") (pinfunction "14_14") (pintype "passive"))
      (node (ref "U1") (pin "32") (pinfunction "GPIO36/SPIIO7/FSPICLK/SUBSPICLK_32") (pintype "passive"))
    )
    (net (code "48") (name "/GPIO37") (class "Default")
      (node (ref "J2") (pin "13") (pinfunction "13_13") (pintype "passive"))
      (node (ref "U1") (pin "33") (pinfunction "GPIO37/SPIDQS/FSPIQ/SUBSPIQ_33") (pintype "passive"))
    )
    (net (code "49") (name "/GPIO38") (class "Default")
      (node (ref "J2") (pin "12") (pinfunction "12_12") (pintype "passive"))
      (node (ref "U1") (pin "34") (pinfunction "GPIO38/FSPIWP/SUBSPIWP_34") (pintype "passive"))
    )
    (net (code "50") (name "/GPIO39") (class "Default")
      (node (ref "J2") (pin "11") (pinfunction "11_11") (pintype "passive"))
      (node (ref "U1") (pin "35") (pinfunction "MTCK/GPIO39/CLK_OUT3/SUBSPICS1_35") (pintype "passive"))
    )
    (net (code "51") (name "/GPIO40") (class "Default")
      (node (ref "J2") (pin "10") (pinfunction "10_10") (pintype "passive"))
      (node (ref "U1") (pin "36") (pinfunction "MTDO/GPIO40/CLK_OUT2_36") (pintype "passive"))
    )
    (net (code "52") (name "/GPIO41") (class "Default")
      (node (ref "J2") (pin "9") (pinfunction "9_9") (pintype "passive"))
      (node (ref "U1") (pin "37") (pinfunction "MTDI/GPIO41/CLK_OUT1_37") (pintype "passive"))
    )
    (net (code "53") (name "/GPIO42") (class "Default")
      (node (ref "J2") (pin "8") (pinfunction "8_8") (pintype "passive"))
      (node (ref "U1") (pin "38") (pinfunction "MTMS/GPIO42_38") (pintype "passive"))
    )
    (net (code "54") (name "/GPIO45") (class "Default")
      (node (ref "J2") (pin "5") (pinfunction "5_5") (pintype "passive"))
      (node (ref "U1") (pin "41") (pinfunction "GPIO45_41") (pintype "passive"))
    )
    (net (code "55") (name "/GPIO46") (class "Default")
      (node (ref "J2") (pin "4") (pinfunction "4_4") (pintype "passive"))
      (node (ref "U1") (pin "44") (pinfunction "GPIO46_44") (pintype "passive"))
    )
    (net (code "56") (name "/GPIO47") (class "Default")
      (node (ref "J2") (pin "23") (pinfunction "23_23") (pintype "passive"))
      (node (ref "U1") (pin "27") (pinfunction "GPIO47/SPICLK_P_DIFF/SUBSPICLK_P_DIFF_27") (pintype "passive"))
    )
    (net (code "57") (name "/GPIO48") (class "Default")
      (node (ref "J2") (pin "22") (pinfunction "22_22") (pintype "passive"))
      (node (ref "U1") (pin "30") (pinfunction "GPIO48/SPICLK_N_DIFF/SUBSPICLK_N_DIFF_30") (pintype "passive"))
    )
    (net (code "58") (name "/RTS_FTDI") (class "Default")
      (node (ref "Q1") (pin "2") (pinfunction "E_2") (pintype "passive"))
      (node (ref "R22") (pin "1") (pinfunction "1_1") (pintype "passive"))
      (node (ref "U2") (pin "19") (pinfunction "~{RTS}_19") (pintype "passive"))
    )
    (net (code "59") (name "/RXD_FTDI") (class "Default")
      (node (ref "R19") (pin "2") (pinfunction "2_2") (pintype "passive"))
      (node (ref "U2") (pin "1") (pinfunction "RXD_1") (pintype "passive"))
    )
    (net (code "60") (name "/TXD_FTDI") (class "Default")
      (node (ref "R20") (pin "2") (pinfunction "2_2") (pintype "passive"))
      (node (ref "U2") (pin "17") (pinfunction "TXD_17") (pintype "passive"))
    )
    (net (code "61") (name "/U0RXD") (class "Default")
      (node (ref "J2") (pin "6") (pinfunction "6_6") (pintype "passive"))
      (node (ref "R20") (pin "1") (pinfunction "1_1") (pintype "passive"))
      (node (ref "U1") (pin "40") (pinfunction "U0RXD/GPIO44/CLK_OUT2_40") (pintype "passive"))
    )
    (net (code "62") (name "/U0TXD") (class "Default")
      (node (ref "J2") (pin "7") (pinfunction "7_7") (pintype "passive"))
      (node (ref "R19") (pin "1") (pinfunction "1_1") (pintype "passive"))
      (node (ref "U1") (pin "39") (pinfunction "U0TXD/GPIO43/CLK_OUT1_39") (pintype "passive"))
    )
    (net (code "63") (name "/VBUS SENSE") (class "Default")
      (node (ref "R10") (pin "1") (pinfunction "1_1") (pintype "passive"))
      (node (ref "R13") (pin "2") (pinfunction "2_2") (pintype "passive"))
      (node (ref "U2") (pin "16") (pinfunction "CBUS3_16") (pintype "passive"))
    )
    (net (code "64") (name "GND") (class "Default")
      (node (ref "C1") (pin "1") (pinfunction "1_1") (pintype "passive"))
      (node (ref "C10") (pin "1") (pinfunction "1_1") (pintype "passive"))
      (node (ref "C11") (pin "1") (pinfunction "1_1") (pintype "passive"))
      (node (ref "C12") (pin "1") (pinfunction "1_1") (pintype "passive"))
      (node (ref "C13") (pin "1") (pinfunction "1_1") (pintype "passive"))
      (node (ref "C14") (pin "1") (pinfunction "1_1") (pintype "passive"))
      (node (ref "C15") (pin "1") (pinfunction "1_1") (pintype "passive"))
      (node (ref "C16") (pin "1") (pinfunction "1_1") (pintype "passive"))
      (node (ref "C17") (pin "1") (pinfunction "1_1") (pintype "passive"))
      (node (ref "C2") (pin "1") (pinfunction "1_1") (pintype "passive"))
      (node (ref "C3") (pin "2") (pinfunction "2_2") (pintype "passive"))
      (node (ref "C4") (pin "1") (pinfunction "1_1") (pintype "passive"))
      (node (ref "C5") (pin "1") (pinfunction "1_1") (pintype "passive"))
      (node (ref "C6") (pin "1") (pinfunction "1_1") (pintype "passive"))
      (node (ref "C7") (pin "1") (pinfunction "1_1") (pintype "passive"))
      (node (ref "C8") (pin "1") (pinfunction "1_1") (pintype "passive"))
      (node (ref "C9") (pin "1") (pinfunction "1_1") (pintype "passive"))
      (node (ref "D1") (pin "1") (pinfunction "1_1") (pintype "passive"))
      (node (ref "D3") (pin "1") (pinfunction "1_1") (pintype "passive"))
      (node (ref "D4") (pin "1") (pinfunction "1_1") (pintype "passive"))
      (node (ref "D5") (pin "1") (pinfunction "1_1") (pintype "passive"))
      (node (ref "D6") (pin "1") (pinfunction "1_1") (pintype "passive"))
      (node (ref "D7") (pin "1") (pinfunction "1_1") (pintype "passive"))
      (node (ref "D8") (pin "1") (pinfunction "1_1") (pintype "passive"))
      (node (ref "J1") (pin "1") (pinfunction "1_1") (pintype "passive"))
      (node (ref "J1") (pin "23") (pinfunction "23_23") (pintype "passive"))
      (node (ref "J2") (pin "2") (pinfunction "2_2") (pintype "passive"))
      (node (ref "J2") (pin "24") (pinfunction "24_24") (pintype "passive"))
      (node (ref "J3") (pin "A1B12") (pinfunction "GND_A1B12_A1B12") (pintype "passive"))
      (node (ref "J3") (pin "B1A12") (pinfunction "GND_B1A12_B1A12") (pintype "passive"))
      (node (ref "J3") (pin "S1") (pinfunction "SHIELD_1_S1") (pintype "passive"))
      (node (ref "J3") (pin "S2") (pinfunction "SHIELD_2_S2") (pintype "passive"))
      (node (ref "J3") (pin "S3") (pinfunction "SHIELD_3_S3") (pintype "passive"))
      (node (ref "J3") (pin "S4") (pinfunction "SHIELD_4_S4") (pintype "passive"))
      (node (ref "J4") (pin "A1B12") (pinfunction "GND_A1B12_A1B12") (pintype "passive"))
      (node (ref "J4") (pin "B1A12") (pinfunction "GND_B1A12_B1A12") (pintype "passive"))
      (node (ref "J4") (pin "S1") (pinfunction "SHIELD_1_S1") (pintype "passive"))
      (node (ref "J4") (pin "S2") (pinfunction "SHIELD_2_S2") (pintype "passive"))
      (node (ref "J4") (pin "S3") (pinfunction "SHIELD_3_S3") (pintype "passive"))
      (node (ref "J4") (pin "S4") (pinfunction "SHIELD_4_S4") (pintype "passive"))
      (node (ref "R11") (pin "1") (pinfunction "1_1") (pintype "passive"))
      (node (ref "R12") (pin "1") (pinfunction "1_1") (pintype "passive"))
      (node (ref "R13") (pin "1") (pinfunction "1_1") (pintype "passive"))
      (node (ref "R14") (pin "1") (pinfunction "1_1") (pintype "passive"))
      (node (ref "R15") (pin "1") (pinfunction "1_1") (pintype "passive"))
      (node (ref "R9") (pin "2") (pinfunction "2_2") (pintype "passive"))
      (node (ref "SW1") (pin "3") (pinfunction "3_3") (pintype "passive"))
      (node (ref "SW1") (pin "4") (pinfunction "4_4") (pintype "passive"))
      (node (ref "SW2") (pin "3") (pinfunction "3_3") (pintype "passive"))
      (node (ref "SW2") (pin "4") (pinfunction "4_4") (pintype "passive"))
      (node (ref "U1") (pin "1") (pinfunction "GND_01_1") (pintype "passive"))
      (node (ref "U1") (pin "2") (pinfunction "GND_02_2") (pintype "passive"))
      (node (ref "U1") (pin "42") (pinfunction "GND_42") (pintype "passive"))
      (node (ref "U1") (pin "43") (pinfunction "GND_43") (pintype "passive"))
      (node (ref "U1") (pin "46") (pinfunction "GND_46_46") (pintype "passive"))
      (node (ref "U1") (pin "47") (pinfunction "GND_47_47") (pintype "passive"))
      (node (ref "U1") (pin "48") (pinfunction "GND_48_48") (pintype "passive"))
      (node (ref "U1") (pin "49") (pinfunction "GND_49_49") (pintype "passive"))
      (node (ref "U1") (pin "50") (pinfunction "GND_50_50") (pintype "passive"))
      (node (ref "U1") (pin "51") (pinfunction "GND_51_51") (pintype "passive"))
      (node (ref "U1") (pin "52") (pinfunction "GND_52_52") (pintype "passive"))
      (node (ref "U1") (pin "53") (pinfunction "GND_53_53") (pintype "passive"))
      (node (ref "U1") (pin "54") (pinfunction "GND_54_54") (pintype "passive"))
      (node (ref "U1") (pin "55") (pinfunction "GND_55_55") (pintype "passive"))
      (node (ref "U1") (pin "56") (pinfunction "GND_56_56") (pintype "passive"))
      (node (ref "U1") (pin "57") (pinfunction "GND_57_57") (pintype "passive"))
      (node (ref "U1") (pin "58") (pinfunction "GND_58_58") (pintype "passive"))
      (node (ref "U1") (pin "59") (pinfunction "GND_59_59") (pintype "passive"))
      (node (ref "U1") (pin "60") (pinfunction "GND_60_60") (pintype "passive"))
      (node (ref "U1") (pin "61") (pinfunction "GND_61_61") (pintype "passive"))
      (node (ref "U1") (pin "62") (pinfunction "GND_62_62") (pintype "passive"))
      (node (ref "U1") (pin "63") (pinfunction "GND_63_63") (pintype "passive"))
      (node (ref "U1") (pin "64") (pinfunction "GND_64_64") (pintype "passive"))
      (node (ref "U1") (pin "65") (pinfunction "GND_65_65") (pintype "passive"))
      (node (ref "U1") (pin "66") (pinfunction "GND_66_66") (pintype "passive"))
      (node (ref "U1") (pin "67") (pinfunction "GND_67_67") (pintype "passive"))
      (node (ref "U1") (pin "68") (pinfunction "GND_68_68") (pintype "passive"))
      (node (ref "U1") (pin "69") (pinfunction "GND_69_69") (pintype "passive"))
      (node (ref "U1") (pin "70") (pinfunction "GND_70_70") (pintype "passive"))
      (node (ref "U1") (pin "71") (pinfunction "GND_71_71") (pintype "passive"))
      (node (ref "U1") (pin "72") (pinfunction "GND_72_72") (pintype "passive"))
      (node (ref "U1") (pin "73") (pinfunction "GND_73_73") (pintype "passive"))
      (node (ref "U2") (pin "13") (pinfunction "GND_13") (pintype "passive"))
      (node (ref "U2") (pin "21") (pinfunction "GND_21") (pintype "passive"))
      (node (ref "U2") (pin "3") (pinfunction "GND_3") (pintype "passive"))
      (node (ref "U3") (pin "2") (pinfunction "GND_2") (pintype "power_in"))
      (node (ref "U3") (pin "4") (pinfunction "GND_4") (pintype "power_in"))
    )
    (net (code "65") (name "Net-(D1-Pad2)") (class "Default")
      (node (ref "D1") (pin "2") (pinfunction "2_2") (pintype "passive"))
      (node (ref "R3") (pin "1") (pinfunction "1_1") (pintype "passive"))
    )
    (net (code "66") (name "Net-(D2-Pad2)") (class "Default")
      (node (ref "D2") (pin "2") (pinfunction "2_2") (pintype "passive"))
      (node (ref "R4") (pin "1") (pinfunction "1_1") (pintype "passive"))
    )
    (net (code "67") (name "Net-(J3-CC1)") (class "Default")
      (node (ref "J3") (pin "A5") (pinfunction "CC1_A5") (pintype "passive"))
      (node (ref "R12") (pin "2") (pinfunction "2_2") (pintype "passive"))
    )
    (net (code "68") (name "Net-(J3-CC2)") (class "Default")
      (node (ref "J3") (pin "B5") (pinfunction "CC2_B5") (pintype "passive"))
      (node (ref "R11") (pin "2") (pinfunction "2_2") (pintype "passive"))
    )
    (net (code "69") (name "Net-(J4-CC1)") (class "Default")
      (node (ref "J4") (pin "A5") (pinfunction "CC1_A5") (pintype "passive"))
      (node (ref "R15") (pin "2") (pinfunction "2_2") (pintype "passive"))
    )
    (net (code "70") (name "Net-(J4-CC2)") (class "Default")
      (node (ref "J4") (pin "B5") (pinfunction "CC2_B5") (pintype "passive"))
      (node (ref "R14") (pin "2") (pinfunction "2_2") (pintype "passive"))
    )
    (net (code "71") (name "Net-(Q1-B)") (class "Default")
      (node (ref "Q1") (pin "1") (pinfunction "B_1") (pintype "passive"))
      (node (ref "R16") (pin "2") (pinfunction "2_2") (pintype "passive"))
    )
    (net (code "72") (name "Net-(Q2-B)") (class "Default")
      (node (ref "Q2") (pin "1") (pinfunction "B_1") (pintype "passive"))
      (node (ref "R22") (pin "2") (pinfunction "2_2") (pintype "passive"))
    )
    (net (code "73") (name "Net-(U2-CBUS0)") (class "Default")
      (node (ref "R9") (pin "1") (pinfunction "1_1") (pintype "passive"))
      (node (ref "U2") (pin "15") (pinfunction "CBUS0_15") (pintype "passive"))
    )
    (net (code "74") (name "unconnected-(J1-Pad24)") (class "Default")
      (node (ref "J1") (pin "24") (pinfunction "24_24") (pintype "passive+no_connect"))
    )
    (net (code "75") (name "unconnected-(J3-SBU1-PadA8)") (class "Default")
      (node (ref "J3") (pin "A8") (pinfunction "SBU1_A8") (pintype "passive+no_connect"))
    )
    (net (code "76") (name "unconnected-(J3-SBU2-PadB8)") (class "Default")
      (node (ref "J3") (pin "B8") (pinfunction "SBU2_B8") (pintype "passive+no_connect"))
    )
    (net (code "77") (name "unconnected-(J4-SBU1-PadA8)") (class "Default")
      (node (ref "J4") (pin "A8") (pinfunction "SBU1_A8") (pintype "passive+no_connect"))
    )
    (net (code "78") (name "unconnected-(J4-SBU2-PadB8)") (class "Default")
      (node (ref "J4") (pin "B8") (pinfunction "SBU2_B8") (pintype "passive+no_connect"))
    )
    (net (code "79") (name "unconnected-(U2-CBUS1-Pad14)") (class "Default")
      (node (ref "U2") (pin "14") (pinfunction "CBUS1_14") (pintype "passive"))
    )
    (net (code "80") (name "unconnected-(U2-CBUS2-Pad7)") (class "Default")
      (node (ref "U2") (pin "7") (pinfunction "CBUS2_7") (pintype "passive"))
    )
    (net (code "81") (name "unconnected-(U2-~{CTS}-Pad6)") (class "Default")
      (node (ref "U2") (pin "6") (pinfunction "~{CTS}_6") (pintype "passive+no_connect"))
    )
    (net (code "82") (name "unconnected-(U2-~{DCD}-Pad5)") (class "Default")
      (node (ref "U2") (pin "5") (pinfunction "~{DCD}_5") (pintype "passive+no_connect"))
    )
    (net (code "83") (name "unconnected-(U2-~{DSR}-Pad4)") (class "Default")
      (node (ref "U2") (pin "4") (pinfunction "~{DSR}_4") (pintype "passive+no_connect"))
    )
    (net (code "84") (name "unconnected-(U2-~{RI}-Pad2)") (class "Default")
      (node (ref "U2") (pin "2") (pinfunction "~{RI}_2") (pintype "passive+no_connect"))
    )
  )
)
